# numeric2.net
KiCad netlist of a schematic drawn in EAGLE
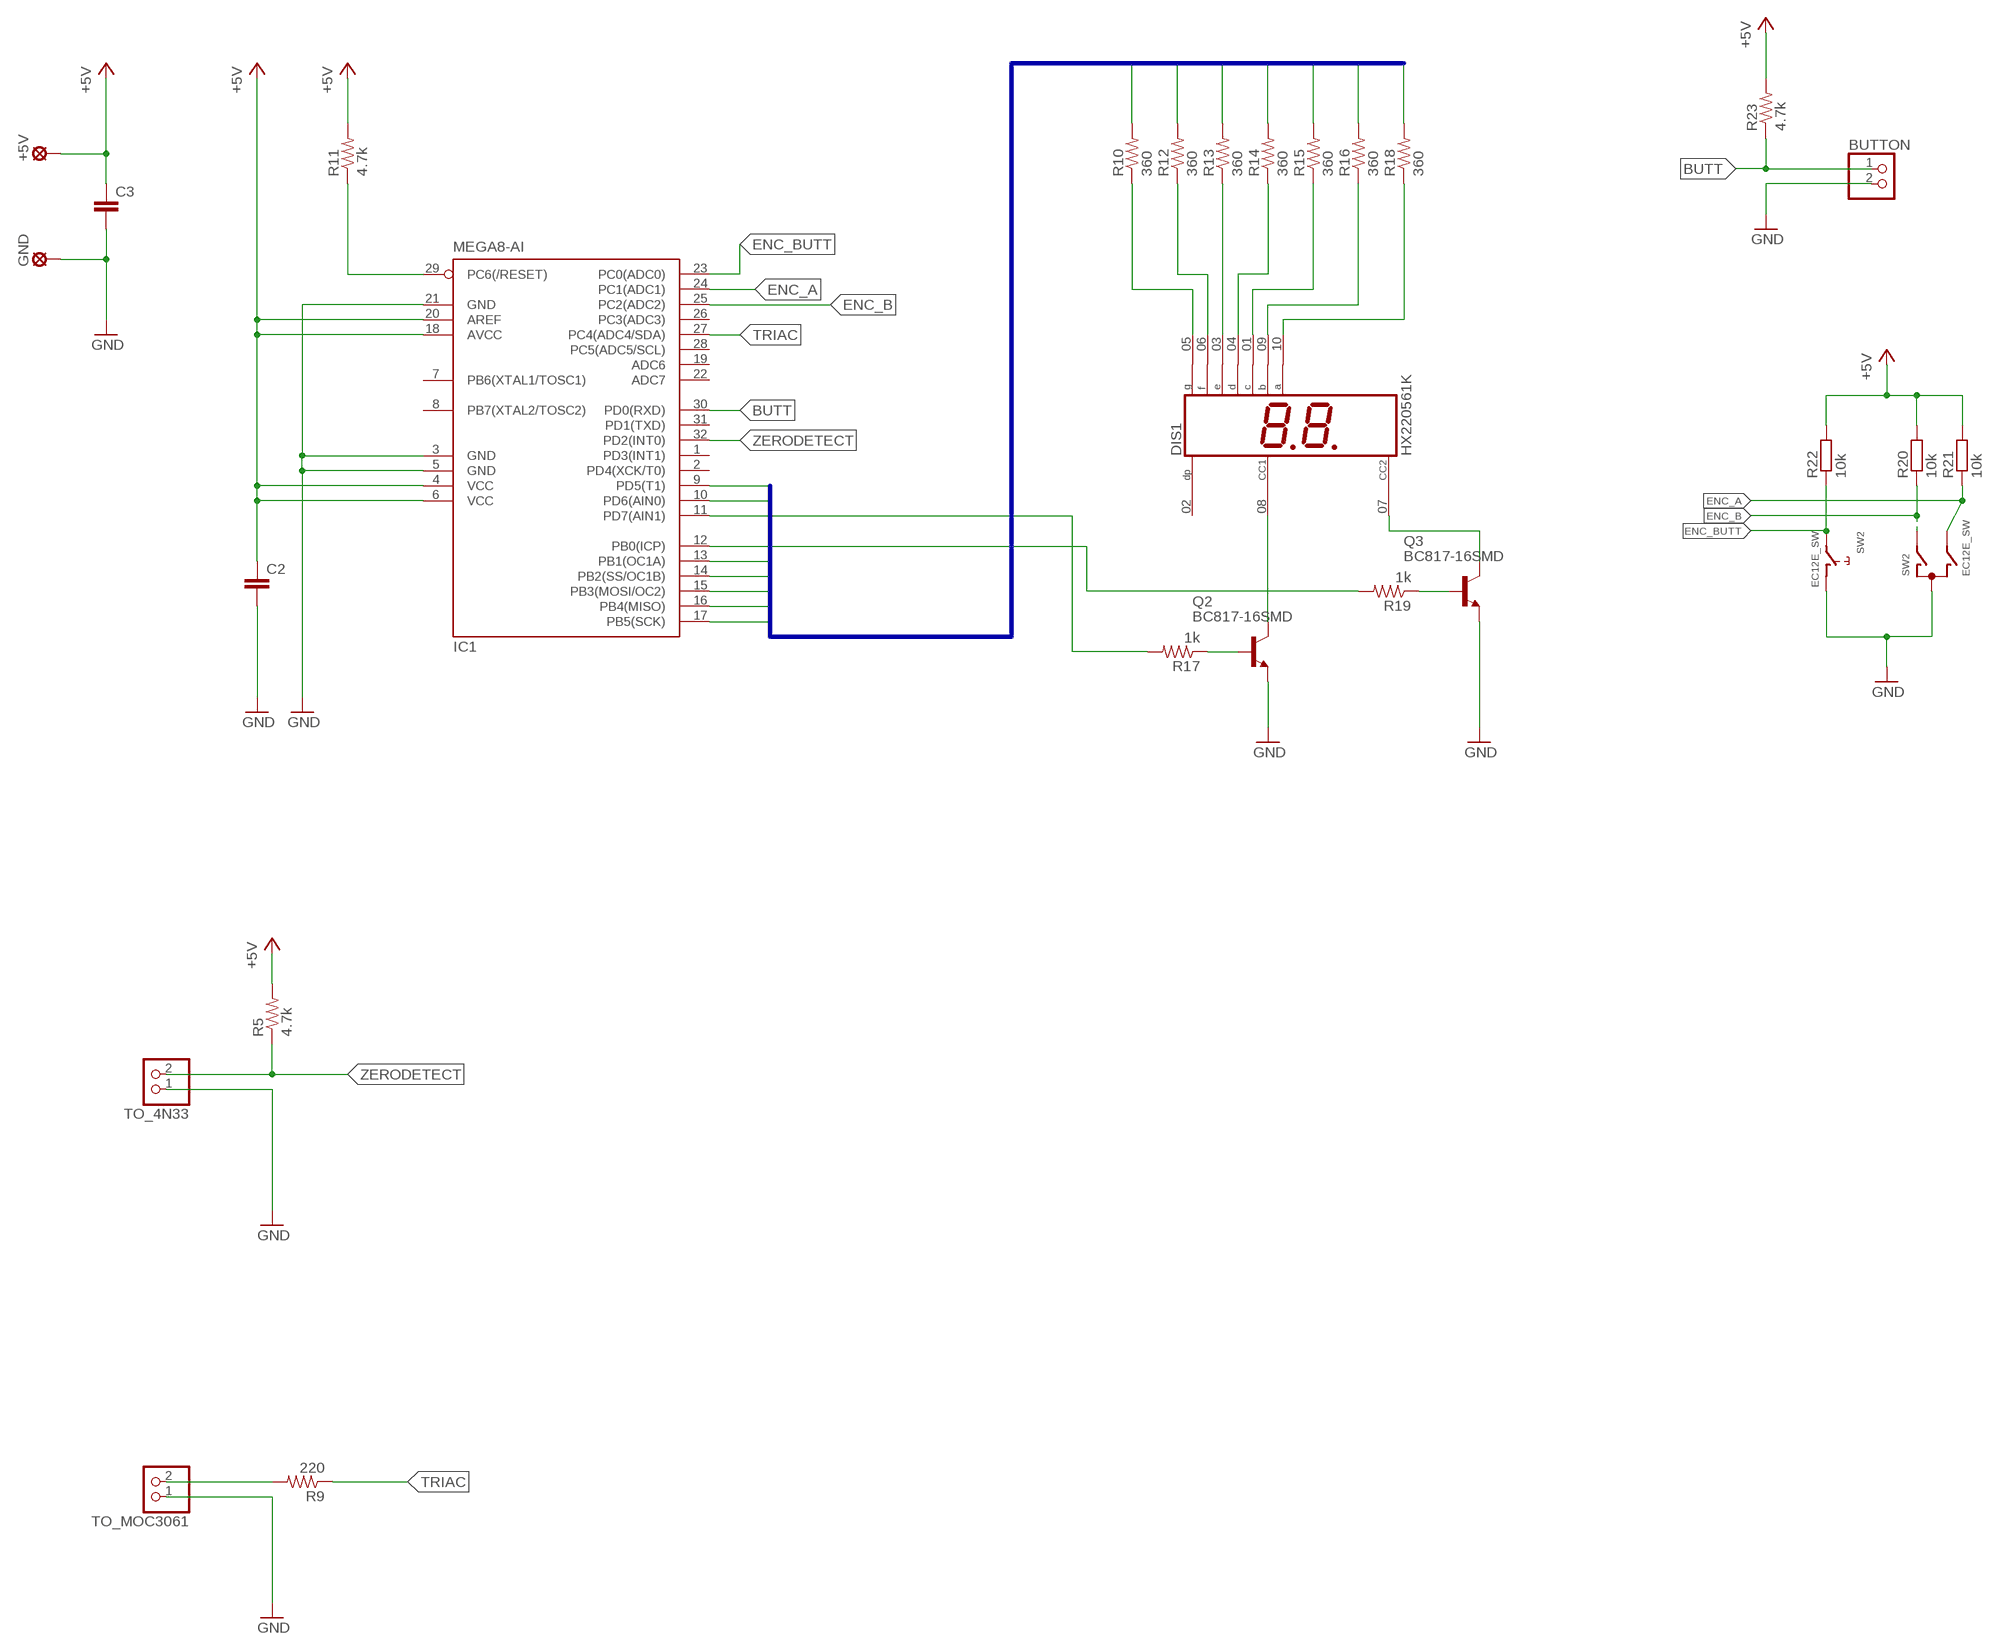
[diagram p0: schematic, sheet 1]

(export (version "E")
  (design (tool "Eeschema 10.0.6"))
  (components
    (comp (ref "+5V")
      (value "LSP10")
      (footprint "eagle-import:LSP10")
      (libsource (lib "eagle-import") (part "LSP10"))
    )
    (comp (ref "BUTTON")
      (value "PINHD-1X2")
      (footprint "eagle-import:1X02")
      (libsource (lib "eagle-import") (part "PINHD-1X2"))
    )
    (comp (ref "C2")
      (value "C-EUC1210K")
      (footprint "eagle-import:C1210K")
      (libsource (lib "eagle-import") (part "C-EUC1210K"))
    )
    (comp (ref "C3")
      (value "C-EUC1210K")
      (footprint "eagle-import:C1210K")
      (libsource (lib "eagle-import") (part "C-EUC1210K"))
    )
    (comp (ref "DIS1")
      (value "HX220561K")
      (footprint "eagle-import:HX220561K")
      (libsource (lib "eagle-import") (part "HX220561K"))
    )
    (comp (ref "GND")
      (value "LSP10")
      (footprint "eagle-import:LSP10")
      (libsource (lib "eagle-import") (part "LSP10"))
    )
    (comp (ref "IC1")
      (value "MEGA8-AI")
      (footprint "eagle-import:TQFP32-08")
      (fields (field (name "MPN") "ATMEGA8-16AU"))
      (libsource (lib "eagle-import") (part "MEGA8-AI"))
    )
    (comp (ref "Q2")
      (value "BC817-16SMD")
      (footprint "eagle-import:SOT23-BEC")
      (libsource (lib "eagle-import") (part "BC817SMD-16"))
    )
    (comp (ref "Q3")
      (value "BC817-16SMD")
      (footprint "eagle-import:SOT23-BEC")
      (libsource (lib "eagle-import") (part "BC817SMD-16"))
    )
    (comp (ref "R5")
      (value "4.7k")
      (footprint "eagle-import:M1206")
      (libsource (lib "eagle-import") (part "R-US_M1206"))
    )
    (comp (ref "R9")
      (value "220")
      (footprint "eagle-import:M1206")
      (libsource (lib "eagle-import") (part "R-US_M1206"))
    )
    (comp (ref "R10")
      (value "360")
      (footprint "eagle-import:M1206")
      (libsource (lib "eagle-import") (part "R-US_M1206"))
    )
    (comp (ref "R11")
      (value "4.7k")
      (footprint "eagle-import:M1206")
      (libsource (lib "eagle-import") (part "R-US_M1206"))
    )
    (comp (ref "R12")
      (value "360")
      (footprint "eagle-import:M1206")
      (libsource (lib "eagle-import") (part "R-US_M1206"))
    )
    (comp (ref "R13")
      (value "360")
      (footprint "eagle-import:M1206")
      (libsource (lib "eagle-import") (part "R-US_M1206"))
    )
    (comp (ref "R14")
      (value "360")
      (footprint "eagle-import:M1206")
      (libsource (lib "eagle-import") (part "R-US_M1206"))
    )
    (comp (ref "R15")
      (value "360")
      (footprint "eagle-import:M1206")
      (libsource (lib "eagle-import") (part "R-US_M1206"))
    )
    (comp (ref "R16")
      (value "360")
      (footprint "eagle-import:M1206")
      (libsource (lib "eagle-import") (part "R-US_M1206"))
    )
    (comp (ref "R17")
      (value "1k")
      (footprint "eagle-import:M1206")
      (libsource (lib "eagle-import") (part "R-US_M1206"))
    )
    (comp (ref "R18")
      (value "360")
      (footprint "eagle-import:M1206")
      (libsource (lib "eagle-import") (part "R-US_M1206"))
    )
    (comp (ref "R19")
      (value "1k")
      (footprint "eagle-import:M1206")
      (libsource (lib "eagle-import") (part "R-US_M1206"))
    )
    (comp (ref "R20")
      (value "10k")
      (footprint "eagle-import:R1206")
      (libsource (lib "eagle-import") (part "R-EU_R1206"))
    )
    (comp (ref "R21")
      (value "10k")
      (footprint "eagle-import:R1206")
      (libsource (lib "eagle-import") (part "R-EU_R1206"))
    )
    (comp (ref "R22")
      (value "10k")
      (footprint "eagle-import:R1206")
      (libsource (lib "eagle-import") (part "R-EU_R1206"))
    )
    (comp (ref "R23")
      (value "4.7k")
      (footprint "eagle-import:M1206")
      (libsource (lib "eagle-import") (part "R-US_M1206"))
    )
    (comp (ref "SW2")
      (value "EC12E_SW")
      (footprint "eagle-import:ALPS_EC12E_SW")
      (fields (field (name "MPN") "EC12E2424407"))
      (libsource (lib "eagle-import") (part "EC12E_SW"))
    )
    (comp (ref "TO_4N33")
      (value "PINHD-1X2")
      (footprint "eagle-import:1X02")
      (libsource (lib "eagle-import") (part "PINHD-1X2"))
    )
    (comp (ref "TO_MOC3061")
      (value "PINHD-1X2")
      (footprint "eagle-import:1X02")
      (libsource (lib "eagle-import") (part "PINHD-1X2"))
    )
  )
  (nets
    (net (code "1") (name "+5V") (class "Default")
      (node (ref "+5V") (pin "MP") (pinfunction "MP_MP") (pintype "passive"))
      (node (ref "C2") (pin "1") (pinfunction "1_1") (pintype "passive"))
      (node (ref "C3") (pin "1") (pinfunction "1_1") (pintype "passive"))
      (node (ref "IC1") (pin "18") (pinfunction "AVCC_18") (pintype "power_in"))
      (node (ref "IC1") (pin "20") (pinfunction "AREF_20") (pintype "passive"))
      (node (ref "IC1") (pin "4") (pinfunction "VCC_4") (pintype "power_in"))
      (node (ref "IC1") (pin "6") (pinfunction "VCC_6") (pintype "power_in"))
      (node (ref "R11") (pin "2") (pinfunction "2_2") (pintype "passive"))
      (node (ref "R20") (pin "2") (pinfunction "2_2") (pintype "passive"))
      (node (ref "R21") (pin "2") (pinfunction "2_2") (pintype "passive"))
      (node (ref "R22") (pin "2") (pinfunction "2_2") (pintype "passive"))
      (node (ref "R23") (pin "2") (pinfunction "2_2") (pintype "passive"))
      (node (ref "R5") (pin "2") (pinfunction "2_2") (pintype "passive"))
    )
    (net (code "2") (name "/B0") (class "Default")
      (node (ref "IC1") (pin "10") (pinfunction "PD6(AIN0)_10") (pintype "bidirectional"))
      (node (ref "R16") (pin "2") (pinfunction "2_2") (pintype "passive"))
    )
    (net (code "3") (name "/B1") (class "Default")
      (node (ref "IC1") (pin "9") (pinfunction "PD5(T1)_9") (pintype "bidirectional"))
      (node (ref "R18") (pin "2") (pinfunction "2_2") (pintype "passive"))
    )
    (net (code "4") (name "/B2") (class "Default")
      (node (ref "IC1") (pin "13") (pinfunction "PB1(OC1A)_13") (pintype "bidirectional"))
      (node (ref "R15") (pin "2") (pinfunction "2_2") (pintype "passive"))
    )
    (net (code "5") (name "/B3") (class "Default")
      (node (ref "IC1") (pin "14") (pinfunction "PB2(SS/OC1B)_14") (pintype "bidirectional"))
      (node (ref "R13") (pin "2") (pinfunction "2_2") (pintype "passive"))
    )
    (net (code "6") (name "/B4") (class "Default")
      (node (ref "IC1") (pin "15") (pinfunction "PB3(MOSI/OC2)_15") (pintype "bidirectional"))
      (node (ref "R14") (pin "2") (pinfunction "2_2") (pintype "passive"))
    )
    (net (code "7") (name "/B5") (class "Default")
      (node (ref "IC1") (pin "16") (pinfunction "PB4(MISO)_16") (pintype "bidirectional"))
      (node (ref "R10") (pin "2") (pinfunction "2_2") (pintype "passive"))
    )
    (net (code "8") (name "/B6") (class "Default")
      (node (ref "IC1") (pin "17") (pinfunction "PB5(SCK)_17") (pintype "bidirectional"))
      (node (ref "R12") (pin "2") (pinfunction "2_2") (pintype "passive"))
    )
    (net (code "9") (name "BUTT") (class "Default")
      (node (ref "BUTTON") (pin "1") (pinfunction "1_1") (pintype "passive"))
      (node (ref "IC1") (pin "30") (pinfunction "PD0(RXD)_30") (pintype "bidirectional"))
      (node (ref "R23") (pin "1") (pinfunction "1_1") (pintype "passive"))
    )
    (net (code "10") (name "ENC_A") (class "Default")
      (node (ref "IC1") (pin "24") (pinfunction "PC1(ADC1)_24") (pintype "bidirectional"))
      (node (ref "R21") (pin "1") (pinfunction "1_1") (pintype "passive"))
      (node (ref "SW2") (pin "B") (pinfunction "B_B") (pintype "passive"))
    )
    (net (code "11") (name "ENC_B") (class "Default")
      (node (ref "IC1") (pin "25") (pinfunction "PC2(ADC2)_25") (pintype "bidirectional"))
      (node (ref "R20") (pin "1") (pinfunction "1_1") (pintype "passive"))
      (node (ref "SW2") (pin "A") (pinfunction "A_A") (pintype "passive"))
    )
    (net (code "12") (name "ENC_BUTT") (class "Default")
      (node (ref "IC1") (pin "23") (pinfunction "PC0(ADC0)_23") (pintype "bidirectional"))
      (node (ref "R22") (pin "1") (pinfunction "1_1") (pintype "passive"))
      (node (ref "SW2") (pin "E") (pinfunction "BUTT_E") (pintype "passive"))
    )
    (net (code "13") (name "GND") (class "Default")
      (node (ref "BUTTON") (pin "2") (pinfunction "2_2") (pintype "passive"))
      (node (ref "C2") (pin "2") (pinfunction "2_2") (pintype "passive"))
      (node (ref "C3") (pin "2") (pinfunction "2_2") (pintype "passive"))
      (node (ref "GND") (pin "MP") (pinfunction "MP_MP") (pintype "passive"))
      (node (ref "IC1") (pin "21") (pinfunction "GND_21") (pintype "power_in"))
      (node (ref "IC1") (pin "3") (pinfunction "GND_3") (pintype "power_in"))
      (node (ref "IC1") (pin "5") (pinfunction "GND_5") (pintype "power_in"))
      (node (ref "Q2") (pin "E") (pinfunction "E_E") (pintype "passive"))
      (node (ref "Q3") (pin "E") (pinfunction "E_E") (pintype "passive"))
      (node (ref "SW2") (pin "C") (pinfunction "C_C") (pintype "passive"))
      (node (ref "SW2") (pin "GND@1") (pinfunction "BUTT_GND_GND@1") (pintype "passive"))
      (node (ref "TO_4N33") (pin "1") (pinfunction "1_1") (pintype "passive"))
      (node (ref "TO_MOC3061") (pin "1") (pinfunction "1_1") (pintype "passive"))
    )
    (net (code "14") (name "Net-(DIS1-A)") (class "Default")
      (node (ref "DIS1") (pin "10") (pinfunction "A_10") (pintype "passive"))
      (node (ref "R18") (pin "1") (pinfunction "1_1") (pintype "passive"))
    )
    (net (code "15") (name "Net-(DIS1-B)") (class "Default")
      (node (ref "DIS1") (pin "09") (pinfunction "B_09") (pintype "passive"))
      (node (ref "R16") (pin "1") (pinfunction "1_1") (pintype "passive"))
    )
    (net (code "16") (name "Net-(DIS1-C)") (class "Default")
      (node (ref "DIS1") (pin "01") (pinfunction "C_01") (pintype "passive"))
      (node (ref "R15") (pin "1") (pinfunction "1_1") (pintype "passive"))
    )
    (net (code "17") (name "Net-(DIS1-CC1)") (class "Default")
      (node (ref "DIS1") (pin "08") (pinfunction "CC1_08") (pintype "passive"))
      (node (ref "Q2") (pin "C") (pinfunction "C_C") (pintype "passive"))
    )
    (net (code "18") (name "Net-(DIS1-CC2)") (class "Default")
      (node (ref "DIS1") (pin "07") (pinfunction "CC2_07") (pintype "passive"))
      (node (ref "Q3") (pin "C") (pinfunction "C_C") (pintype "passive"))
    )
    (net (code "19") (name "Net-(DIS1-D)") (class "Default")
      (node (ref "DIS1") (pin "04") (pinfunction "D_04") (pintype "passive"))
      (node (ref "R14") (pin "1") (pinfunction "1_1") (pintype "passive"))
    )
    (net (code "20") (name "Net-(DIS1-E)") (class "Default")
      (node (ref "DIS1") (pin "03") (pinfunction "E_03") (pintype "passive"))
      (node (ref "R13") (pin "1") (pinfunction "1_1") (pintype "passive"))
    )
    (net (code "21") (name "Net-(DIS1-F)") (class "Default")
      (node (ref "DIS1") (pin "06") (pinfunction "F_06") (pintype "passive"))
      (node (ref "R12") (pin "1") (pinfunction "1_1") (pintype "passive"))
    )
    (net (code "22") (name "Net-(DIS1-G)") (class "Default")
      (node (ref "DIS1") (pin "05") (pinfunction "G_05") (pintype "passive"))
      (node (ref "R10") (pin "1") (pinfunction "1_1") (pintype "passive"))
    )
    (net (code "23") (name "Net-(IC1-PB0(ICP))") (class "Default")
      (node (ref "IC1") (pin "12") (pinfunction "PB0(ICP)_12") (pintype "bidirectional"))
      (node (ref "R19") (pin "2") (pinfunction "2_2") (pintype "passive"))
    )
    (net (code "24") (name "Net-(IC1-PC6({slash}RESET))") (class "Default")
      (node (ref "IC1") (pin "29") (pinfunction "PC6(/RESET)_29") (pintype "bidirectional"))
      (node (ref "R11") (pin "1") (pinfunction "1_1") (pintype "passive"))
    )
    (net (code "25") (name "Net-(IC1-PD7(AIN1))") (class "Default")
      (node (ref "IC1") (pin "11") (pinfunction "PD7(AIN1)_11") (pintype "bidirectional"))
      (node (ref "R17") (pin "2") (pinfunction "2_2") (pintype "passive"))
    )
    (net (code "26") (name "Net-(Q2-PadB)") (class "Default")
      (node (ref "Q2") (pin "B") (pinfunction "B_B") (pintype "passive"))
      (node (ref "R17") (pin "1") (pinfunction "1_1") (pintype "passive"))
    )
    (net (code "27") (name "Net-(Q3-PadB)") (class "Default")
      (node (ref "Q3") (pin "B") (pinfunction "B_B") (pintype "passive"))
      (node (ref "R19") (pin "1") (pinfunction "1_1") (pintype "passive"))
    )
    (net (code "28") (name "Net-(R9-Pad2)") (class "Default")
      (node (ref "R9") (pin "2") (pinfunction "2_2") (pintype "passive"))
      (node (ref "TO_MOC3061") (pin "2") (pinfunction "2_2") (pintype "passive"))
    )
    (net (code "29") (name "TRIAC") (class "Default")
      (node (ref "IC1") (pin "27") (pinfunction "PC4(ADC4/SDA)_27") (pintype "bidirectional"))
      (node (ref "R9") (pin "1") (pinfunction "1_1") (pintype "passive"))
    )
    (net (code "30") (name "ZERODETECT") (class "Default")
      (node (ref "IC1") (pin "32") (pinfunction "PD2(INT0)_32") (pintype "bidirectional"))
      (node (ref "R5") (pin "1") (pinfunction "1_1") (pintype "passive"))
      (node (ref "TO_4N33") (pin "2") (pinfunction "2_2") (pintype "passive"))
    )
    (net (code "31") (name "unconnected-(DIS1-DP-Pad02)") (class "Default")
      (node (ref "DIS1") (pin "02") (pinfunction "DP_02") (pintype "passive"))
    )
    (net (code "32") (name "unconnected-(IC1-ADC6-Pad19)") (class "Default")
      (node (ref "IC1") (pin "19") (pinfunction "ADC6_19") (pintype "bidirectional"))
    )
    (net (code "33") (name "unconnected-(IC1-ADC7-Pad22)") (class "Default")
      (node (ref "IC1") (pin "22") (pinfunction "ADC7_22") (pintype "bidirectional"))
    )
    (net (code "34") (name "unconnected-(IC1-PB6(XTAL1{slash}TOSC1)-Pad7)") (class "Default")
      (node (ref "IC1") (pin "7") (pinfunction "PB6(XTAL1/TOSC1)_7") (pintype "bidirectional"))
    )
    (net (code "35") (name "unconnected-(IC1-PB7(XTAL2{slash}TOSC2)-Pad8)") (class "Default")
      (node (ref "IC1") (pin "8") (pinfunction "PB7(XTAL2/TOSC2)_8") (pintype "bidirectional"))
    )
    (net (code "36") (name "unconnected-(IC1-PC3(ADC3)-Pad26)") (class "Default")
      (node (ref "IC1") (pin "26") (pinfunction "PC3(ADC3)_26") (pintype "bidirectional"))
    )
    (net (code "37") (name "unconnected-(IC1-PC5(ADC5{slash}SCL)-Pad28)") (class "Default")
      (node (ref "IC1") (pin "28") (pinfunction "PC5(ADC5/SCL)_28") (pintype "bidirectional"))
    )
    (net (code "38") (name "unconnected-(IC1-PD1(TXD)-Pad31)") (class "Default")
      (node (ref "IC1") (pin "31") (pinfunction "PD1(TXD)_31") (pintype "bidirectional"))
    )
    (net (code "39") (name "unconnected-(IC1-PD3(INT1)-Pad1)") (class "Default")
      (node (ref "IC1") (pin "1") (pinfunction "PD3(INT1)_1") (pintype "bidirectional"))
    )
    (net (code "40") (name "unconnected-(IC1-PD4(XCK{slash}T0)-Pad2)") (class "Default")
      (node (ref "IC1") (pin "2") (pinfunction "PD4(XCK/T0)_2") (pintype "bidirectional"))
    )
  )
)
